# 2014_IHM.net
KiCad netlist of a schematic drawn in Altium Designer
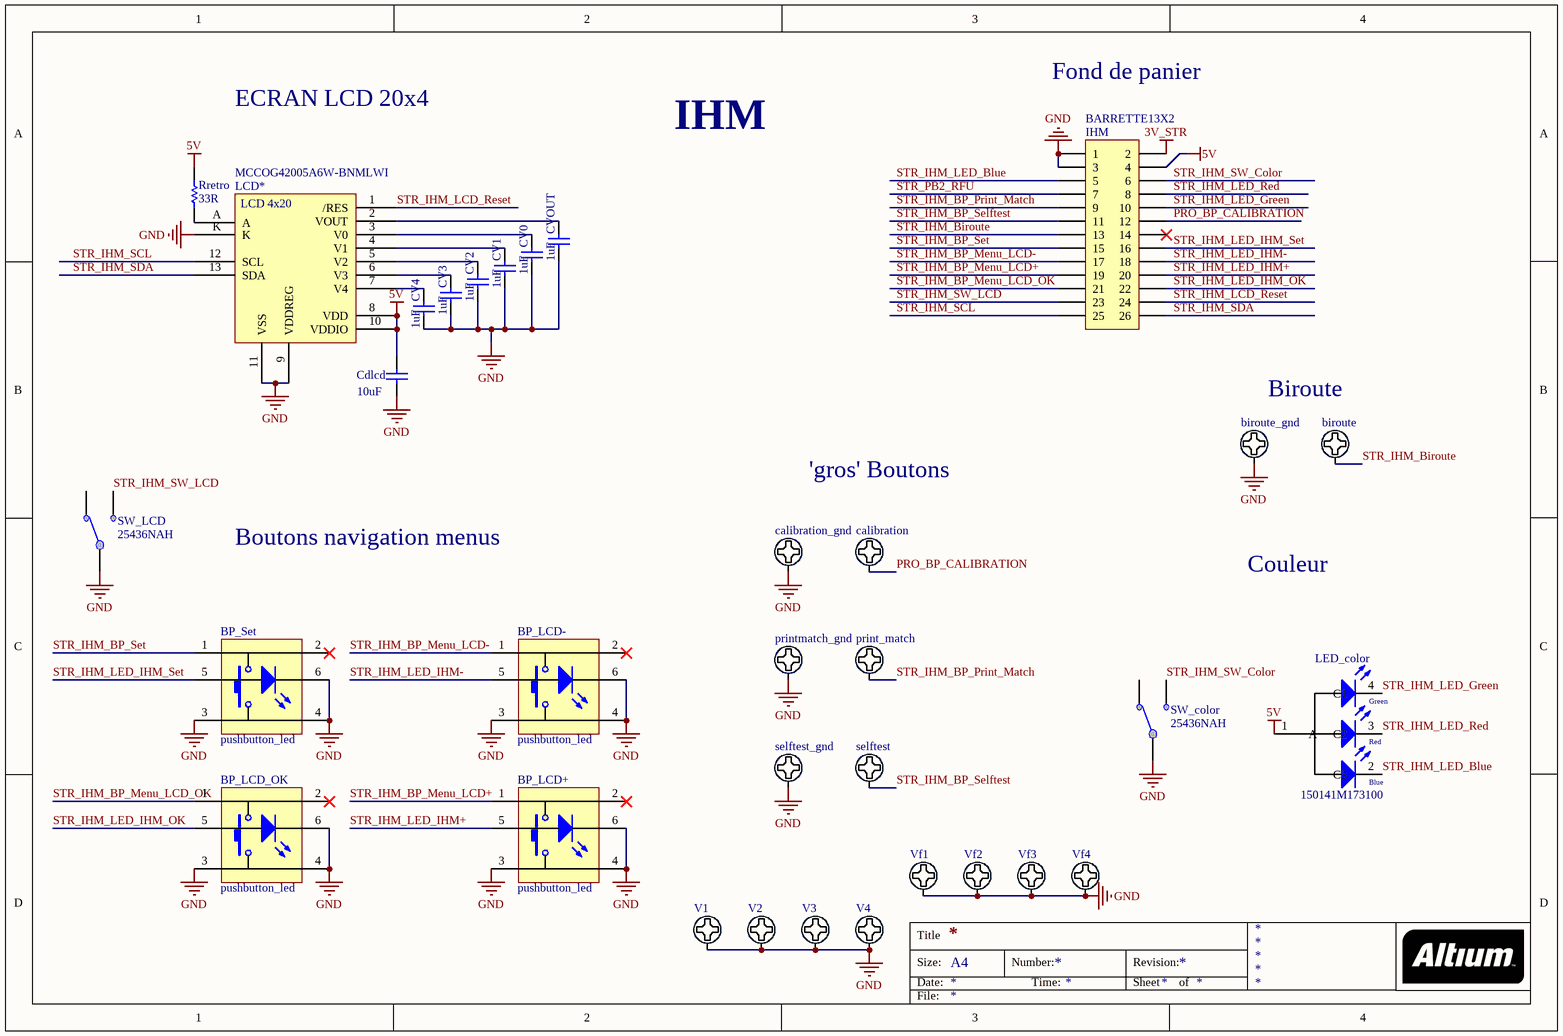
[diagram p0: 2014_IHM.SchDoc]

(export (version "E")
  (design (tool "Eeschema 10.0.6"))
  (components
    (comp (ref "biroute")
      (value "Pad_M3")
      (footprint "PAD_CMS_5.08x2.54")
      (description "Vis M3 X 6mm _TORX_Tête 6mm")
      (fields (field (name "PUBLISHER") "Damien Guitton"))
      (libsource (lib "_ROBOT") (part "Vis M3 X 6mm _TORX_Tête 6mm"))
    )
    (comp (ref "biroute_gnd")
      (value "Pad_M3")
      (footprint "PAD_CMS_5.08x2.54")
      (description "Vis M3 X 6mm _TORX_Tête 6mm")
      (fields (field (name "PUBLISHER") "Damien Guitton"))
      (libsource (lib "_ROBOT") (part "Vis M3 X 6mm _TORX_Tête 6mm"))
    )
    (comp (ref "BP_LCD+")
      (value "pushbutton_led")
      (footprint "PUSHBUTTON_LED_FlecheDroite")
      (libsource (lib "_ROBOT") (part "pushbutton_led"))
    )
    (comp (ref "BP_LCD-")
      (value "pushbutton_led")
      (footprint "PUSHBUTTON_LED_FlecheGauche")
      (libsource (lib "_ROBOT") (part "pushbutton_led"))
    )
    (comp (ref "BP_LCD_OK")
      (value "pushbutton_led")
      (footprint "PUSHBUTTON_LED_OK")
      (libsource (lib "_ROBOT") (part "pushbutton_led"))
    )
    (comp (ref "BP_Set")
      (value "pushbutton_led")
      (footprint "PUSHBUTTON_LED_SET")
      (libsource (lib "_ROBOT") (part "pushbutton_led"))
    )
    (comp (ref "calibration")
      (value "Pad_M3")
      (footprint "PAD_CMS_5.08x2.54")
      (description "Vis M3 X 6mm _TORX_Tête 6mm")
      (fields (field (name "PUBLISHER") "Damien Guitton"))
      (libsource (lib "_ROBOT") (part "Vis M3 X 6mm _TORX_Tête 6mm"))
    )
    (comp (ref "calibration_gnd")
      (value "Pad_M3")
      (footprint "PAD_CMS_5.08x2.54")
      (description "Vis M3 X 6mm _TORX_Tête 6mm")
      (fields (field (name "PUBLISHER") "Damien Guitton"))
      (libsource (lib "_ROBOT") (part "Vis M3 X 6mm _TORX_Tête 6mm"))
    )
    (comp (ref "Cdlcd")
      (value "10uF")
      (footprint "C0805_N")
      (description "Capacitor")
      (fields (field (name "PUBLISHER") "Altium Limited"))
      (libsource (lib "_ROBOT") (part "Condensateur"))
    )
    (comp (ref "CV0")
      (value "1uF")
      (footprint "C0805_N")
      (description "Capacitor")
      (fields (field (name "PUBLISHER") "Altium Limited"))
      (libsource (lib "_ROBOT") (part "Condensateur"))
    )
    (comp (ref "CV1")
      (value "1uF")
      (footprint "C0805_N")
      (description "Capacitor")
      (fields (field (name "PUBLISHER") "Altium Limited"))
      (libsource (lib "_ROBOT") (part "Condensateur"))
    )
    (comp (ref "CV2")
      (value "1uF")
      (footprint "C0805_N")
      (description "Capacitor")
      (fields (field (name "PUBLISHER") "Altium Limited"))
      (libsource (lib "_ROBOT") (part "Condensateur"))
    )
    (comp (ref "CV3")
      (value "1uF")
      (footprint "C0805_N")
      (description "Capacitor")
      (fields (field (name "PUBLISHER") "Altium Limited"))
      (libsource (lib "_ROBOT") (part "Condensateur"))
    )
    (comp (ref "CV4")
      (value "1uF")
      (footprint "C0805_N")
      (description "Capacitor")
      (fields (field (name "PUBLISHER") "Altium Limited"))
      (libsource (lib "_ROBOT") (part "Condensateur"))
    )
    (comp (ref "CVOUT")
      (value "1uF")
      (footprint "C0805_N")
      (description "Capacitor")
      (fields (field (name "PUBLISHER") "Altium Limited"))
      (libsource (lib "_ROBOT") (part "Condensateur"))
    )
    (comp (ref "IHM")
      (value "BARRETTE13X2")
      (footprint "HE10/26_M_D_BP")
      (description "Header, 13-Pin, Dual row")
      (fields (field (name "PUBLISHER") "Altium Limited"))
      (libsource (lib "Connecteur") (part "BARRETTE13X2"))
    )
    (comp (ref "LCD*")
      (value "MCCOG42005A6W-BNMLWI")
      (footprint "LCD_4X20_MIDAS")
      (libsource (lib "_ROBOT") (part "LCD_MIDAS_4x20"))
    )
    (comp (ref "LED_color")
      (value "150141M173100")
      (footprint "3528")
      (description "SMD Full-Color Top LED, WL-SFTW, Red & Green & Blue")
      (fields
        (field (name "MANUFACTURER") "Würth Elektronik eiSos GmbH")
        (field (name "CREATED BY") "Christin Otto")
      )
      (libsource (lib "WL-SFTW") (part "WL-SFTW 3528 150141M173100"))
    )
    (comp (ref "printmatch_gnd")
      (value "Pad_M3")
      (footprint "PAD_CMS_5.08x2.54")
      (description "Vis M3 X 6mm _TORX_Tête 6mm")
      (fields (field (name "PUBLISHER") "Damien Guitton"))
      (libsource (lib "_ROBOT") (part "Vis M3 X 6mm _TORX_Tête 6mm"))
    )
    (comp (ref "print_match")
      (value "Pad_M3")
      (footprint "PAD_CMS_5.08x2.54")
      (description "Vis M3 X 6mm _TORX_Tête 6mm")
      (fields (field (name "PUBLISHER") "Damien Guitton"))
      (libsource (lib "_ROBOT") (part "Vis M3 X 6mm _TORX_Tête 6mm"))
    )
    (comp (ref "Rretro")
      (value "33R")
      (footprint "R1206_N")
      (description "Resistor")
      (fields (field (name "PUBLISHER") "Altium Limited"))
      (libsource (lib "_ROBOT") (part "Resistor"))
    )
    (comp (ref "selftest")
      (value "Pad_M3")
      (footprint "PAD_CMS_5.08x2.54")
      (description "Vis M3 X 6mm _TORX_Tête 6mm")
      (fields (field (name "PUBLISHER") "Damien Guitton"))
      (libsource (lib "_ROBOT") (part "Vis M3 X 6mm _TORX_Tête 6mm"))
    )
    (comp (ref "selftest_gnd")
      (value "Pad_M3")
      (footprint "PAD_CMS_5.08x2.54")
      (description "Vis M3 X 6mm _TORX_Tête 6mm")
      (fields (field (name "PUBLISHER") "Damien Guitton"))
      (libsource (lib "_ROBOT") (part "Vis M3 X 6mm _TORX_Tête 6mm"))
    )
    (comp (ref "SW_color")
      (value "25436NAH")
      (footprint "SW_UNIPOL_DROIT - APEM 523X B")
      (description "Switch unipolaire a levier")
      (libsource (lib "DG_Interrupteur") (part "SW SPDT- APEM Série 523x"))
    )
    (comp (ref "SW_LCD")
      (value "25436NAH")
      (footprint "SW_UNIPOL_DROIT - APEM 523X B")
      (description "Switch unipolaire a levier")
      (libsource (lib "DG_Interrupteur") (part "SW SPDT- APEM Série 523x"))
    )
    (comp (ref "V1")
      (value "Pad_M3")
      (footprint "M3x6mm")
      (description "Vis M3 X 6mm _TORX_Tête 6mm")
      (fields (field (name "PUBLISHER") "Damien Guitton"))
      (libsource (lib "_ROBOT") (part "Vis M3 X 6mm _TORX_Tête 6mm"))
    )
    (comp (ref "V2")
      (value "Pad_M3")
      (footprint "M3x6mm")
      (description "Vis M3 X 6mm _TORX_Tête 6mm")
      (fields (field (name "PUBLISHER") "Damien Guitton"))
      (libsource (lib "_ROBOT") (part "Vis M3 X 6mm _TORX_Tête 6mm"))
    )
    (comp (ref "V3")
      (value "Pad_M3")
      (footprint "M3x6mm")
      (description "Vis M3 X 6mm _TORX_Tête 6mm")
      (fields (field (name "PUBLISHER") "Damien Guitton"))
      (libsource (lib "_ROBOT") (part "Vis M3 X 6mm _TORX_Tête 6mm"))
    )
    (comp (ref "V4")
      (value "Pad_M3")
      (footprint "M3x6mm")
      (description "Vis M3 X 6mm _TORX_Tête 6mm")
      (fields (field (name "PUBLISHER") "Damien Guitton"))
      (libsource (lib "_ROBOT") (part "Vis M3 X 6mm _TORX_Tête 6mm"))
    )
    (comp (ref "Vf1")
      (value "Pad_M3")
      (footprint "M3x6mm")
      (description "Vis M3 X 6mm _TORX_Tête 6mm")
      (fields (field (name "PUBLISHER") "Damien Guitton"))
      (libsource (lib "_ROBOT") (part "Vis M3 X 6mm _TORX_Tête 6mm"))
    )
    (comp (ref "Vf2")
      (value "Pad_M3")
      (footprint "M3x6mm")
      (description "Vis M3 X 6mm _TORX_Tête 6mm")
      (fields (field (name "PUBLISHER") "Damien Guitton"))
      (libsource (lib "_ROBOT") (part "Vis M3 X 6mm _TORX_Tête 6mm"))
    )
    (comp (ref "Vf3")
      (value "Pad_M3")
      (footprint "M3x6mm")
      (description "Vis M3 X 6mm _TORX_Tête 6mm")
      (fields (field (name "PUBLISHER") "Damien Guitton"))
      (libsource (lib "_ROBOT") (part "Vis M3 X 6mm _TORX_Tête 6mm"))
    )
    (comp (ref "Vf4")
      (value "Pad_M3")
      (footprint "M3x6mm")
      (description "Vis M3 X 6mm _TORX_Tête 6mm")
      (fields (field (name "PUBLISHER") "Damien Guitton"))
      (libsource (lib "_ROBOT") (part "Vis M3 X 6mm _TORX_Tête 6mm"))
    )
  )
  (nets
    (net (code "1") (name "/PRO_BP_CALIBRATION") (class "Default")
      (node (ref "IHM") (pin "12") (pinfunction "12_12") (pintype "passive"))
      (node (ref "calibration") (pin "1") (pinfunction "1_1") (pintype "passive"))
    )
    (net (code "2") (name "/STR_IHM_BP_Menu_LCD+") (class "Default")
      (node (ref "BP_LCD+") (pin "1") (pinfunction "1_1") (pintype "passive"))
      (node (ref "IHM") (pin "19") (pinfunction "19_19") (pintype "passive"))
    )
    (net (code "3") (name "/STR_IHM_BP_Menu_LCD-") (class "Default")
      (node (ref "BP_LCD-") (pin "1") (pinfunction "1_1") (pintype "passive"))
      (node (ref "IHM") (pin "17") (pinfunction "17_17") (pintype "passive"))
    )
    (net (code "4") (name "/STR_IHM_BP_Menu_LCD_OK") (class "Default")
      (node (ref "BP_LCD_OK") (pin "1") (pinfunction "1_1") (pintype "passive"))
      (node (ref "IHM") (pin "21") (pinfunction "21_21") (pintype "passive"))
    )
    (net (code "5") (name "/STR_IHM_BP_Print_Match") (class "Default")
      (node (ref "IHM") (pin "9") (pinfunction "9_9") (pintype "passive"))
      (node (ref "print_match") (pin "1") (pinfunction "1_1") (pintype "passive"))
    )
    (net (code "6") (name "/STR_IHM_BP_Selftest") (class "Default")
      (node (ref "IHM") (pin "11") (pinfunction "11_11") (pintype "passive"))
      (node (ref "selftest") (pin "1") (pinfunction "1_1") (pintype "passive"))
    )
    (net (code "7") (name "/STR_IHM_BP_Set") (class "Default")
      (node (ref "BP_Set") (pin "1") (pinfunction "1_1") (pintype "passive"))
      (node (ref "IHM") (pin "15") (pinfunction "15_15") (pintype "passive"))
    )
    (net (code "8") (name "/STR_IHM_Biroute") (class "Default")
      (node (ref "IHM") (pin "13") (pinfunction "13_13") (pintype "passive"))
      (node (ref "biroute") (pin "1") (pinfunction "1_1") (pintype "passive"))
    )
    (net (code "9") (name "/STR_IHM_LCD_Reset") (class "Default")
      (node (ref "IHM") (pin "24") (pinfunction "24_24") (pintype "passive"))
      (node (ref "LCD*") (pin "1") (pinfunction "/RES_1") (pintype "passive"))
    )
    (net (code "10") (name "/STR_IHM_LED_Blue") (class "Default")
      (node (ref "IHM") (pin "5") (pinfunction "5_5") (pintype "passive"))
      (node (ref "LED_color") (pin "2") (pinfunction "C3_2") (pintype "passive"))
    )
    (net (code "11") (name "/STR_IHM_LED_Green") (class "Default")
      (node (ref "IHM") (pin "10") (pinfunction "10_10") (pintype "passive"))
      (node (ref "LED_color") (pin "4") (pinfunction "C1_4") (pintype "passive"))
    )
    (net (code "12") (name "/STR_IHM_LED_IHM+") (class "Default")
      (node (ref "BP_LCD+") (pin "5") (pinfunction "+_5") (pintype "passive"))
      (node (ref "IHM") (pin "20") (pinfunction "20_20") (pintype "passive"))
    )
    (net (code "13") (name "/STR_IHM_LED_IHM-") (class "Default")
      (node (ref "BP_LCD-") (pin "5") (pinfunction "+_5") (pintype "passive"))
      (node (ref "IHM") (pin "18") (pinfunction "18_18") (pintype "passive"))
    )
    (net (code "14") (name "/STR_IHM_LED_IHM_OK") (class "Default")
      (node (ref "BP_LCD_OK") (pin "5") (pinfunction "+_5") (pintype "passive"))
      (node (ref "IHM") (pin "22") (pinfunction "22_22") (pintype "passive"))
    )
    (net (code "15") (name "/STR_IHM_LED_IHM_Set") (class "Default")
      (node (ref "BP_Set") (pin "5") (pinfunction "+_5") (pintype "passive"))
      (node (ref "IHM") (pin "16") (pinfunction "16_16") (pintype "passive"))
    )
    (net (code "16") (name "/STR_IHM_LED_Red") (class "Default")
      (node (ref "IHM") (pin "8") (pinfunction "8_8") (pintype "passive"))
      (node (ref "LED_color") (pin "3") (pinfunction "C2_3") (pintype "passive"))
    )
    (net (code "17") (name "/STR_IHM_SCL") (class "Default")
      (node (ref "IHM") (pin "25") (pinfunction "25_25") (pintype "passive"))
      (node (ref "LCD*") (pin "12") (pinfunction "SCL_12") (pintype "passive"))
    )
    (net (code "18") (name "/STR_IHM_SDA") (class "Default")
      (node (ref "IHM") (pin "26") (pinfunction "26_26") (pintype "passive"))
      (node (ref "LCD*") (pin "13") (pinfunction "SDA_13") (pintype "passive"))
    )
    (net (code "19") (name "/STR_IHM_SW_Color") (class "Default")
      (node (ref "IHM") (pin "6") (pinfunction "6_6") (pintype "passive"))
      (node (ref "SW_color") (pin "NO1") (pinfunction "NO1_NO1") (pintype "passive"))
    )
    (net (code "20") (name "/STR_IHM_SW_LCD") (class "Default")
      (node (ref "IHM") (pin "23") (pinfunction "23_23") (pintype "passive"))
      (node (ref "SW_LCD") (pin "NO1") (pinfunction "NO1_NO1") (pintype "passive"))
    )
    (net (code "21") (name "/STR_PB2_RFU") (class "Default")
      (node (ref "IHM") (pin "7") (pinfunction "7_7") (pintype "passive"))
    )
    (net (code "22") (name "3V_STR") (class "Default")
      (node (ref "IHM") (pin "2") (pinfunction "2_2") (pintype "passive"))
    )
    (net (code "23") (name "5V") (class "Default")
      (node (ref "Cdlcd") (pin "1") (pinfunction "1_1") (pintype "passive"))
      (node (ref "IHM") (pin "4") (pinfunction "4_4") (pintype "passive"))
      (node (ref "LCD*") (pin "10") (pinfunction "VDDIO_10") (pintype "passive"))
      (node (ref "LCD*") (pin "8") (pinfunction "VDD_8") (pintype "passive"))
      (node (ref "LED_color") (pin "1") (pinfunction "A_1") (pintype "passive"))
      (node (ref "Rretro") (pin "2") (pinfunction "2_2") (pintype "passive"))
    )
    (net (code "24") (name "GND") (class "Default")
      (node (ref "BP_LCD+") (pin "3") (pinfunction "3_3") (pintype "passive"))
      (node (ref "BP_LCD+") (pin "4") (pinfunction "4_4") (pintype "passive"))
      (node (ref "BP_LCD+") (pin "6") (pinfunction "-_6") (pintype "passive"))
      (node (ref "BP_LCD-") (pin "3") (pinfunction "3_3") (pintype "passive"))
      (node (ref "BP_LCD-") (pin "4") (pinfunction "4_4") (pintype "passive"))
      (node (ref "BP_LCD-") (pin "6") (pinfunction "-_6") (pintype "passive"))
      (node (ref "BP_LCD_OK") (pin "3") (pinfunction "3_3") (pintype "passive"))
      (node (ref "BP_LCD_OK") (pin "4") (pinfunction "4_4") (pintype "passive"))
      (node (ref "BP_LCD_OK") (pin "6") (pinfunction "-_6") (pintype "passive"))
      (node (ref "BP_Set") (pin "3") (pinfunction "3_3") (pintype "passive"))
      (node (ref "BP_Set") (pin "4") (pinfunction "4_4") (pintype "passive"))
      (node (ref "BP_Set") (pin "6") (pinfunction "-_6") (pintype "passive"))
      (node (ref "CV0") (pin "2") (pinfunction "2_2") (pintype "passive"))
      (node (ref "CV1") (pin "2") (pinfunction "2_2") (pintype "passive"))
      (node (ref "CV2") (pin "2") (pinfunction "2_2") (pintype "passive"))
      (node (ref "CV3") (pin "2") (pinfunction "2_2") (pintype "passive"))
      (node (ref "CV4") (pin "2") (pinfunction "2_2") (pintype "passive"))
      (node (ref "CVOUT") (pin "2") (pinfunction "2_2") (pintype "passive"))
      (node (ref "Cdlcd") (pin "2") (pinfunction "2_2") (pintype "passive"))
      (node (ref "IHM") (pin "1") (pinfunction "1_1") (pintype "passive"))
      (node (ref "IHM") (pin "3") (pinfunction "3_3") (pintype "passive"))
      (node (ref "LCD*") (pin "11") (pinfunction "VSS_11") (pintype "passive"))
      (node (ref "LCD*") (pin "9") (pinfunction "VDDREG_9") (pintype "passive"))
      (node (ref "LCD*") (pin "K") (pinfunction "K_K") (pintype "passive"))
      (node (ref "SW_LCD") (pin "COMMON1") (pinfunction "COMMON1_COMMON1") (pintype "passive"))
      (node (ref "SW_color") (pin "COMMON1") (pinfunction "COMMON1_COMMON1") (pintype "passive"))
      (node (ref "V1") (pin "1") (pinfunction "1_1") (pintype "passive"))
      (node (ref "V2") (pin "1") (pinfunction "1_1") (pintype "passive"))
      (node (ref "V3") (pin "1") (pinfunction "1_1") (pintype "passive"))
      (node (ref "V4") (pin "1") (pinfunction "1_1") (pintype "passive"))
      (node (ref "Vf1") (pin "1") (pinfunction "1_1") (pintype "passive"))
      (node (ref "Vf2") (pin "1") (pinfunction "1_1") (pintype "passive"))
      (node (ref "Vf3") (pin "1") (pinfunction "1_1") (pintype "passive"))
      (node (ref "Vf4") (pin "1") (pinfunction "1_1") (pintype "passive"))
      (node (ref "biroute_gnd") (pin "1") (pinfunction "1_1") (pintype "passive"))
      (node (ref "calibration_gnd") (pin "1") (pinfunction "1_1") (pintype "passive"))
      (node (ref "printmatch_gnd") (pin "1") (pinfunction "1_1") (pintype "passive"))
      (node (ref "selftest_gnd") (pin "1") (pinfunction "1_1") (pintype "passive"))
    )
    (net (code "25") (name "Net-(LCD*-PadA)") (class "Default")
      (node (ref "LCD*") (pin "A") (pinfunction "A_A") (pintype "passive"))
      (node (ref "Rretro") (pin "1") (pinfunction "1_1") (pintype "passive"))
    )
    (net (code "26") (name "Net-(LCD*-V0)") (class "Default")
      (node (ref "CV0") (pin "1") (pinfunction "1_1") (pintype "passive"))
      (node (ref "LCD*") (pin "3") (pinfunction "V0_3") (pintype "passive"))
    )
    (net (code "27") (name "Net-(LCD*-V1)") (class "Default")
      (node (ref "CV1") (pin "1") (pinfunction "1_1") (pintype "passive"))
      (node (ref "LCD*") (pin "4") (pinfunction "V1_4") (pintype "passive"))
    )
    (net (code "28") (name "Net-(LCD*-V2)") (class "Default")
      (node (ref "CV2") (pin "1") (pinfunction "1_1") (pintype "passive"))
      (node (ref "LCD*") (pin "5") (pinfunction "V2_5") (pintype "passive"))
    )
    (net (code "29") (name "Net-(LCD*-V3)") (class "Default")
      (node (ref "CV3") (pin "1") (pinfunction "1_1") (pintype "passive"))
      (node (ref "LCD*") (pin "6") (pinfunction "V3_6") (pintype "passive"))
    )
    (net (code "30") (name "Net-(LCD*-V4)") (class "Default")
      (node (ref "CV4") (pin "1") (pinfunction "1_1") (pintype "passive"))
      (node (ref "LCD*") (pin "7") (pinfunction "V4_7") (pintype "passive"))
    )
    (net (code "31") (name "Net-(LCD*-VOUT)") (class "Default")
      (node (ref "CVOUT") (pin "1") (pinfunction "1_1") (pintype "passive"))
      (node (ref "LCD*") (pin "2") (pinfunction "VOUT_2") (pintype "passive"))
    )
    (net (code "32") (name "unconnected-(BP_LCD+-3-Pad2)") (class "Default")
      (node (ref "BP_LCD+") (pin "2") (pinfunction "3_2") (pintype "passive+no_connect"))
    )
    (net (code "33") (name "unconnected-(BP_LCD--3-Pad2)") (class "Default")
      (node (ref "BP_LCD-") (pin "2") (pinfunction "3_2") (pintype "passive+no_connect"))
    )
    (net (code "34") (name "unconnected-(BP_LCD_OK-3-Pad2)") (class "Default")
      (node (ref "BP_LCD_OK") (pin "2") (pinfunction "3_2") (pintype "passive+no_connect"))
    )
    (net (code "35") (name "unconnected-(BP_Set-3-Pad2)") (class "Default")
      (node (ref "BP_Set") (pin "2") (pinfunction "3_2") (pintype "passive+no_connect"))
    )
    (net (code "36") (name "unconnected-(IHM-Pad14)") (class "Default")
      (node (ref "IHM") (pin "14") (pinfunction "14_14") (pintype "passive+no_connect"))
    )
    (net (code "37") (name "unconnected-(SW_LCD-PadNC1)") (class "Default")
      (node (ref "SW_LCD") (pin "NC1") (pinfunction "NC1_NC1") (pintype "passive"))
    )
    (net (code "38") (name "unconnected-(SW_color-PadNC1)") (class "Default")
      (node (ref "SW_color") (pin "NC1") (pinfunction "NC1_NC1") (pintype "passive"))
    )
  )
)
